# Grove_-_Air_quality_sensor_v1_3.net
KiCad netlist of a schematic drawn in EAGLE
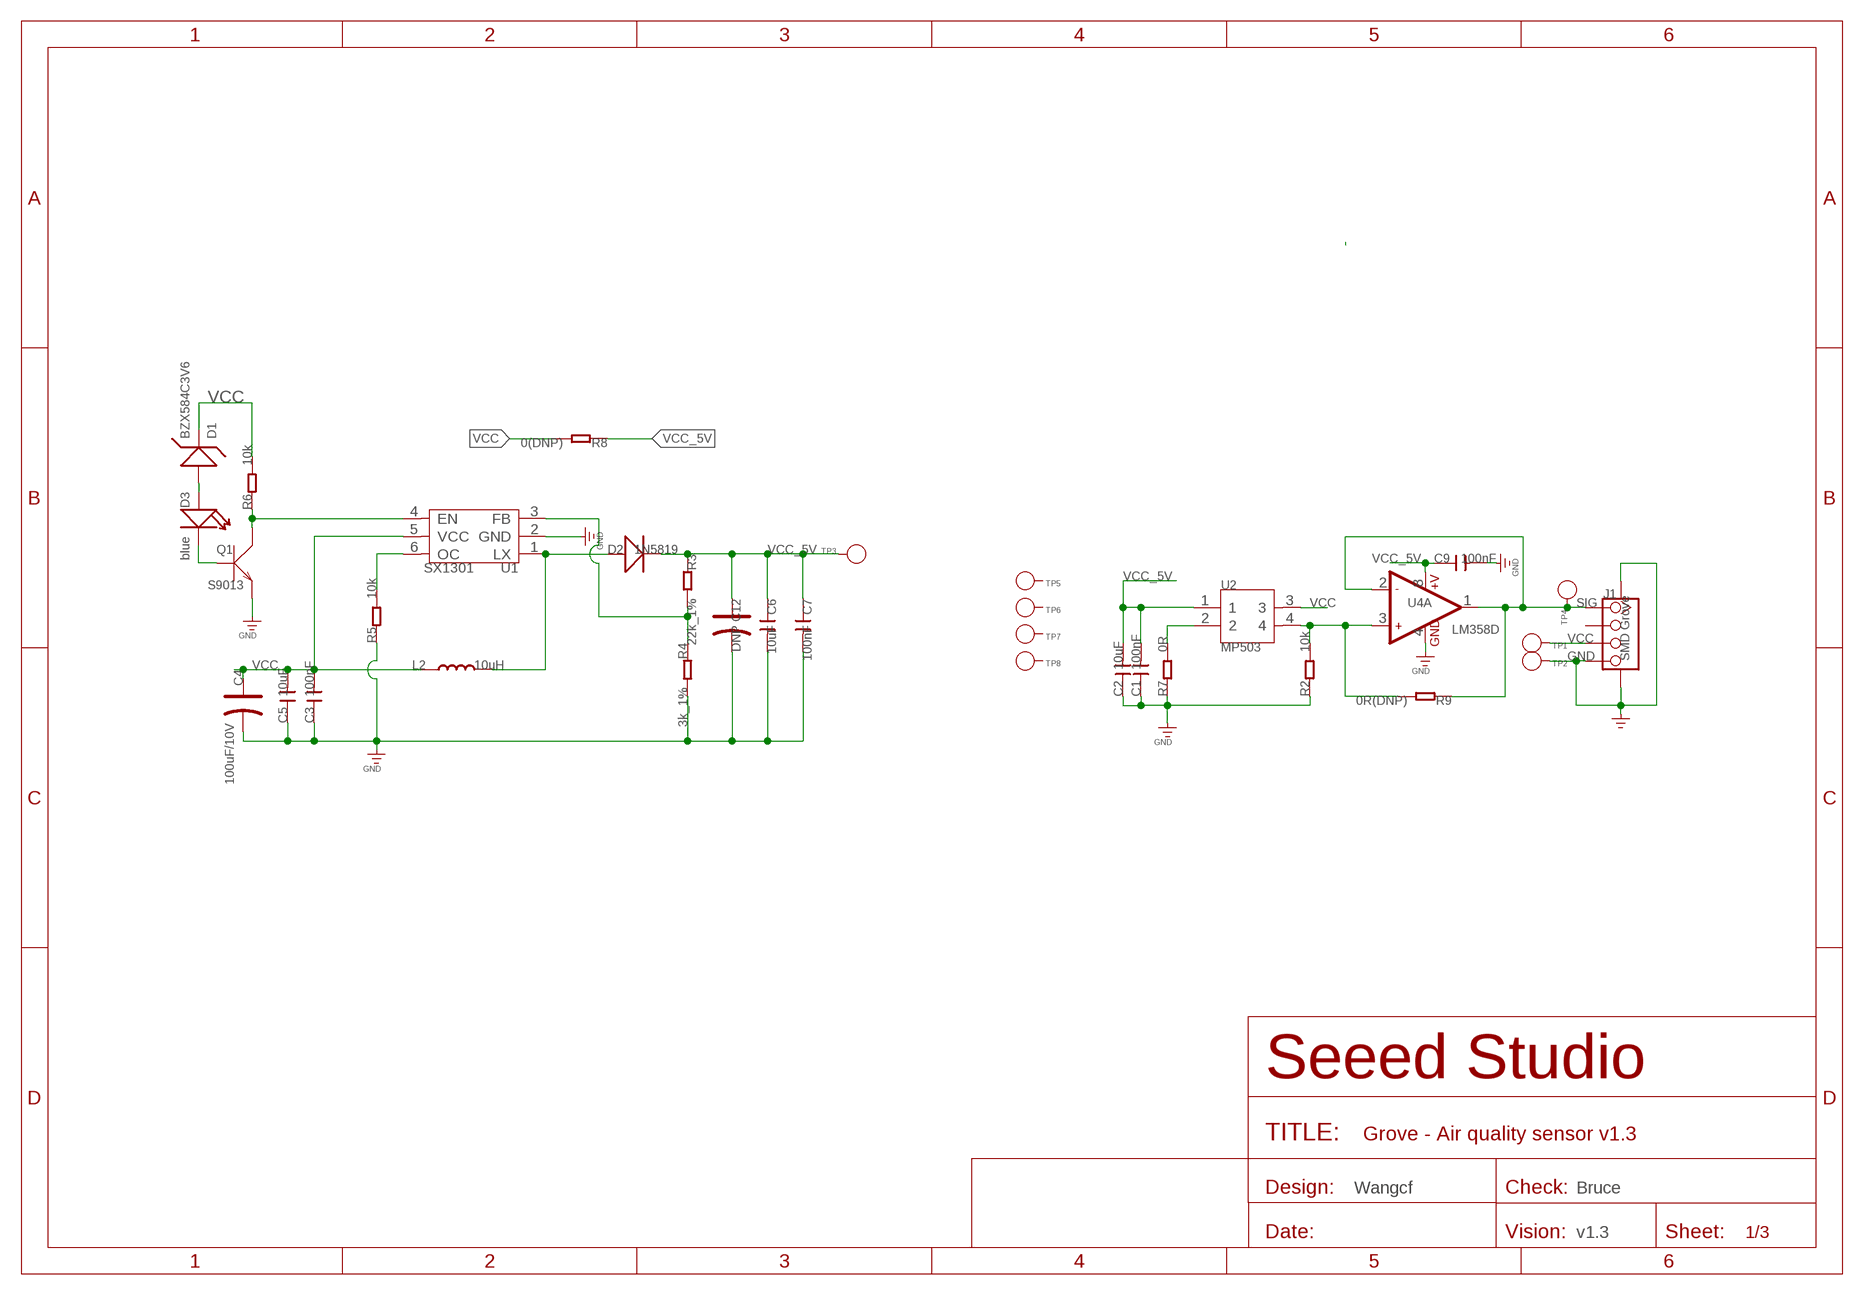
[diagram p0: schematic, sheet 1]
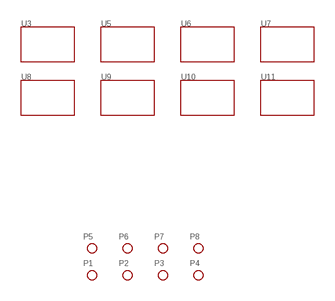
[diagram p1: schematic, sheet 3]

(export (version "E")
  (design (tool "Eeschema 10.0.6"))
  (components
    (comp (ref "P1")
      (value "PAD-MARK")
      (footprint "eagle-import:ROUND-MARK-1.0")
      (fields (field (name "PARTNO") "DNP"))
      (libsource (lib "eagle-import") (part "PAD-MARK"))
    )
    (comp (ref "P2")
      (value "PAD-MARK")
      (footprint "eagle-import:ROUND-MARK-1.0")
      (fields (field (name "PARTNO") "DNP"))
      (libsource (lib "eagle-import") (part "PAD-MARK"))
    )
    (comp (ref "P3")
      (value "PAD-MARK")
      (footprint "eagle-import:ROUND-MARK-1.0")
      (fields (field (name "PARTNO") "DNP"))
      (libsource (lib "eagle-import") (part "PAD-MARK"))
    )
    (comp (ref "P4")
      (value "PAD-MARK")
      (footprint "eagle-import:ROUND-MARK-1.0")
      (fields (field (name "PARTNO") "DNP"))
      (libsource (lib "eagle-import") (part "PAD-MARK"))
    )
    (comp (ref "P5")
      (value "PAD-MARK")
      (footprint "eagle-import:ROUND-MARK-1.0")
      (fields (field (name "PARTNO") "DNP"))
      (libsource (lib "eagle-import") (part "PAD-MARK"))
    )
    (comp (ref "P6")
      (value "PAD-MARK")
      (footprint "eagle-import:ROUND-MARK-1.0")
      (fields (field (name "PARTNO") "DNP"))
      (libsource (lib "eagle-import") (part "PAD-MARK"))
    )
    (comp (ref "P7")
      (value "PAD-MARK")
      (footprint "eagle-import:ROUND-MARK-1.0")
      (fields (field (name "PARTNO") "DNP"))
      (libsource (lib "eagle-import") (part "PAD-MARK"))
    )
    (comp (ref "P8")
      (value "PAD-MARK")
      (footprint "eagle-import:ROUND-MARK-1.0")
      (fields (field (name "PARTNO") "DNP"))
      (libsource (lib "eagle-import") (part "PAD-MARK"))
    )
    (comp (ref "U3")
      (value "TWIG'2U'")
      (footprint "eagle-import:GROVE-TEST-PLATFORM")
      (libsource (lib "eagle-import") (part "TWIG'2U'"))
    )
    (comp (ref "U5")
      (value "TWIG'2U'")
      (footprint "eagle-import:GROVE-TEST-PLATFORM")
      (libsource (lib "eagle-import") (part "TWIG'2U'"))
    )
    (comp (ref "U6")
      (value "TWIG'2U'")
      (footprint "eagle-import:GROVE-TEST-PLATFORM")
      (libsource (lib "eagle-import") (part "TWIG'2U'"))
    )
    (comp (ref "U7")
      (value "TWIG'2U'")
      (footprint "eagle-import:GROVE-TEST-PLATFORM")
      (libsource (lib "eagle-import") (part "TWIG'2U'"))
    )
    (comp (ref "U8")
      (value "TWIG'2U'")
      (footprint "eagle-import:GROVE-TEST-PLATFORM")
      (libsource (lib "eagle-import") (part "TWIG'2U'"))
    )
    (comp (ref "U9")
      (value "TWIG'2U'")
      (footprint "eagle-import:GROVE-TEST-PLATFORM")
      (libsource (lib "eagle-import") (part "TWIG'2U'"))
    )
    (comp (ref "U10")
      (value "TWIG'2U'")
      (footprint "eagle-import:GROVE-TEST-PLATFORM")
      (libsource (lib "eagle-import") (part "TWIG'2U'"))
    )
    (comp (ref "U11")
      (value "TWIG'2U'")
      (footprint "eagle-import:GROVE-TEST-PLATFORM")
      (libsource (lib "eagle-import") (part "TWIG'2U'"))
    )
    (comp (ref "C1")
      (value "100nF")
      (footprint "eagle-import:C0603")
      (libsource (lib "eagle-import") (part "C-0603"))
    )
    (comp (ref "C2")
      (value "10uF")
      (footprint "eagle-import:C0805")
      (libsource (lib "eagle-import") (part "C-0805"))
    )
    (comp (ref "C3")
      (value "100nF")
      (footprint "eagle-import:C0603")
      (libsource (lib "eagle-import") (part "C-0603"))
    )
    (comp (ref "C4")
      (value "100uF/10V")
      (footprint "eagle-import:AVX-B")
      (libsource (lib "eagle-import") (part "CAP-AVX-B"))
    )
    (comp (ref "C5")
      (value "10uF")
      (footprint "eagle-import:C0805")
      (libsource (lib "eagle-import") (part "C-0805"))
    )
    (comp (ref "C6")
      (value "10uF")
      (footprint "eagle-import:C0805")
      (libsource (lib "eagle-import") (part "C-0805"))
    )
    (comp (ref "C7")
      (value "100nF")
      (footprint "eagle-import:C0603")
      (libsource (lib "eagle-import") (part "C-0603"))
    )
    (comp (ref "C9")
      (value "100nF")
      (footprint "eagle-import:C0603")
      (libsource (lib "eagle-import") (part "C-0603"))
    )
    (comp (ref "C12")
      (value "DNP")
      (footprint "eagle-import:AVX-B")
      (libsource (lib "eagle-import") (part "CAP-AVX-B"))
    )
    (comp (ref "D1")
      (value "BZX584C3V6")
      (footprint "eagle-import:SOD-523")
      (libsource (lib "eagle-import") (part "D-ZENER-2P'BZX584CX'"))
    )
    (comp (ref "D2")
      (value "1N5819")
      (footprint "eagle-import:DO-214AC")
      (libsource (lib "eagle-import") (part "D'SMA'"))
    )
    (comp (ref "D3")
      (value "blue")
      (footprint "eagle-import:LED-0603")
      (libsource (lib "eagle-import") (part "LED'0603'"))
    )
    (comp (ref "J1")
      (value "SMD Grove")
      (footprint "eagle-import:4P-SMD-2.0")
      (libsource (lib "eagle-import") (part "TWIG-4P-2.0-SMD-FEMALE-REINFORCE'DD'"))
    )
    (comp (ref "L2")
      (value "10uH")
      (footprint "eagle-import:SD32-4R7MC")
      (libsource (lib "eagle-import") (part "CD32'4R7'"))
    )
    (comp (ref "Q1")
      (value "S9013")
      (footprint "eagle-import:SOT-23")
      (libsource (lib "eagle-import") (part "TRANSISTOR-NPN-SOT23"))
    )
    (comp (ref "R2")
      (value "10k")
      (footprint "eagle-import:R0603")
      (libsource (lib "eagle-import") (part "R-0603"))
    )
    (comp (ref "R3")
      (value "22k_1%")
      (footprint "eagle-import:R0603")
      (libsource (lib "eagle-import") (part "R-0603"))
    )
    (comp (ref "R4")
      (value "3k_1%")
      (footprint "eagle-import:R0603")
      (libsource (lib "eagle-import") (part "R-0603"))
    )
    (comp (ref "R5")
      (value "10k")
      (footprint "eagle-import:R0603")
      (libsource (lib "eagle-import") (part "R-0603"))
    )
    (comp (ref "R6")
      (value "10k")
      (footprint "eagle-import:R0603")
      (libsource (lib "eagle-import") (part "R-0603"))
    )
    (comp (ref "R7")
      (value "0R")
      (footprint "eagle-import:R0603")
      (libsource (lib "eagle-import") (part "R-0603"))
    )
    (comp (ref "R8")
      (value "0(DNP)")
      (footprint "eagle-import:R0603")
      (libsource (lib "eagle-import") (part "R-0603"))
    )
    (comp (ref "R9")
      (value "0R(DNP)")
      (footprint "eagle-import:R0603")
      (libsource (lib "eagle-import") (part "R-0603"))
    )
    (comp (ref "TP1")
      (value "PAD-TEST-POINT'4545'")
      (footprint "eagle-import:TP_4545")
      (fields (field (name "PARTNO") "DNP"))
      (libsource (lib "eagle-import") (part "PAD-TEST-POINT'4545'"))
    )
    (comp (ref "TP2")
      (value "PAD-TEST-POINT'4545'")
      (footprint "eagle-import:TP_4545")
      (fields (field (name "PARTNO") "DNP"))
      (libsource (lib "eagle-import") (part "PAD-TEST-POINT'4545'"))
    )
    (comp (ref "TP3")
      (value "PAD-TEST-POINT'4545'")
      (footprint "eagle-import:TP_4545")
      (fields (field (name "PARTNO") "DNP"))
      (libsource (lib "eagle-import") (part "PAD-TEST-POINT'4545'"))
    )
    (comp (ref "TP4")
      (value "PAD-TEST-POINT'4545'")
      (footprint "eagle-import:TP_4545")
      (fields (field (name "PARTNO") "DNP"))
      (libsource (lib "eagle-import") (part "PAD-TEST-POINT'4545'"))
    )
    (comp (ref "TP5")
      (value "PAD-TEST-POINT'4545'")
      (footprint "eagle-import:TP_4545")
      (fields (field (name "PARTNO") "DNP"))
      (libsource (lib "eagle-import") (part "PAD-TEST-POINT'4545'"))
    )
    (comp (ref "TP6")
      (value "PAD-TEST-POINT'4545'")
      (footprint "eagle-import:TP_4545")
      (fields (field (name "PARTNO") "DNP"))
      (libsource (lib "eagle-import") (part "PAD-TEST-POINT'4545'"))
    )
    (comp (ref "TP7")
      (value "PAD-TEST-POINT'4545'")
      (footprint "eagle-import:TP_4545")
      (fields (field (name "PARTNO") "DNP"))
      (libsource (lib "eagle-import") (part "PAD-TEST-POINT'4545'"))
    )
    (comp (ref "TP8")
      (value "PAD-TEST-POINT'4545'")
      (footprint "eagle-import:TP_4545")
      (fields (field (name "PARTNO") "DNP"))
      (libsource (lib "eagle-import") (part "PAD-TEST-POINT'4545'"))
    )
    (comp (ref "U1")
      (value "SX1301")
      (footprint "eagle-import:SOT23-6L")
      (libsource (lib "eagle-import") (part "SX1301"))
    )
    (comp (ref "U2")
      (value "MP503")
      (footprint "eagle-import:4P_3.1_9.4_9.4_17MM")
      (libsource (lib "eagle-import") (part "SENSOR-MP503'V1.3'"))
    )
    (comp (ref "U4")
      (value "LM358D")
      (footprint "eagle-import:SO08")
      (libsource (lib "eagle-import") (part "LMV358D"))
    )
  )
  (nets
    (net (code "1") (name "GND") (class "Default")
      (node (ref "C1") (pin "1") (pinfunction "1_1") (pintype "passive"))
      (node (ref "C12") (pin "-") (pinfunction "-_-") (pintype "passive"))
      (node (ref "C2") (pin "1") (pinfunction "1_1") (pintype "passive"))
      (node (ref "C3") (pin "1") (pinfunction "1_1") (pintype "passive"))
      (node (ref "C4") (pin "-") (pinfunction "-_-") (pintype "passive"))
      (node (ref "C5") (pin "1") (pinfunction "1_1") (pintype "passive"))
      (node (ref "C6") (pin "2") (pinfunction "2_2") (pintype "passive"))
      (node (ref "C7") (pin "2") (pinfunction "2_2") (pintype "passive"))
      (node (ref "C9") (pin "2") (pinfunction "2_2") (pintype "passive"))
      (node (ref "J1") (pin "4") (pinfunction "4_4") (pintype "bidirectional"))
      (node (ref "J1") (pin "SS1") (pinfunction "SS1_SS1") (pintype "bidirectional"))
      (node (ref "J1") (pin "SS2") (pinfunction "SS2_SS2") (pintype "bidirectional"))
      (node (ref "Q1") (pin "2") (pinfunction "E_2") (pintype "passive"))
      (node (ref "R2") (pin "1") (pinfunction "1_1") (pintype "passive"))
      (node (ref "R4") (pin "2") (pinfunction "2_2") (pintype "passive"))
      (node (ref "R5") (pin "1") (pinfunction "1_1") (pintype "passive"))
      (node (ref "R7") (pin "1") (pinfunction "1_1") (pintype "passive"))
      (node (ref "TP2") (pin "T") (pinfunction "T_T") (pintype "bidirectional"))
      (node (ref "U1") (pin "2") (pinfunction "GND_2") (pintype "bidirectional"))
      (node (ref "U4") (pin "4") (pinfunction "GND_4") (pintype "power_in"))
    )
    (net (code "2") (name "Net-(D1-Pad+)") (class "Default")
      (node (ref "D1") (pin "+") (pinfunction "+_+") (pintype "bidirectional"))
      (node (ref "D3") (pin "+") (pinfunction "+_+") (pintype "passive"))
    )
    (net (code "3") (name "Net-(D2-+)") (class "Default")
      (node (ref "D2") (pin "1") (pinfunction "+_1") (pintype "passive"))
      (node (ref "L2") (pin "2") (pinfunction "2_2") (pintype "passive"))
      (node (ref "U1") (pin "1") (pinfunction "LX_1") (pintype "bidirectional"))
    )
    (net (code "4") (name "Net-(Q1-B)") (class "Default")
      (node (ref "D3") (pin "-") (pinfunction "-_-") (pintype "passive"))
      (node (ref "Q1") (pin "1") (pinfunction "B_1") (pintype "passive"))
    )
    (net (code "5") (name "Net-(Q1-C)") (class "Default")
      (node (ref "Q1") (pin "3") (pinfunction "C_3") (pintype "passive"))
      (node (ref "R6") (pin "1") (pinfunction "1_1") (pintype "passive"))
      (node (ref "U1") (pin "4") (pinfunction "EN_4") (pintype "bidirectional"))
    )
    (net (code "6") (name "Net-(R7-Pad2)") (class "Default")
      (node (ref "R7") (pin "2") (pinfunction "2_2") (pintype "passive"))
      (node (ref "U2") (pin "2") (pinfunction "2_2") (pintype "bidirectional"))
    )
    (net (code "7") (name "Net-(U1-FB)") (class "Default")
      (node (ref "R3") (pin "2") (pinfunction "2_2") (pintype "passive"))
      (node (ref "R4") (pin "1") (pinfunction "1_1") (pintype "passive"))
      (node (ref "U1") (pin "3") (pinfunction "FB_3") (pintype "bidirectional"))
    )
    (net (code "8") (name "Net-(U1-OC)") (class "Default")
      (node (ref "R5") (pin "2") (pinfunction "2_2") (pintype "passive"))
      (node (ref "U1") (pin "6") (pinfunction "OC_6") (pintype "bidirectional"))
    )
    (net (code "9") (name "Net-(U4A-+IN1)") (class "Default")
      (node (ref "R2") (pin "2") (pinfunction "2_2") (pintype "passive"))
      (node (ref "R9") (pin "2") (pinfunction "2_2") (pintype "passive"))
      (node (ref "U2") (pin "4") (pinfunction "4_4") (pintype "bidirectional"))
      (node (ref "U4") (pin "3") (pinfunction "+IN1_3") (pintype "input"))
    )
    (net (code "10") (name "SIG") (class "Default")
      (node (ref "J1") (pin "1") (pinfunction "1_1") (pintype "bidirectional"))
      (node (ref "R9") (pin "1") (pinfunction "1_1") (pintype "passive"))
      (node (ref "TP4") (pin "T") (pinfunction "T_T") (pintype "bidirectional"))
      (node (ref "U4") (pin "1") (pinfunction "OUT1_1") (pintype "output"))
      (node (ref "U4") (pin "2") (pinfunction "-IN1_2") (pintype "input"))
    )
    (net (code "11") (name "VCC") (class "Default")
      (node (ref "C3") (pin "2") (pinfunction "2_2") (pintype "passive"))
      (node (ref "C4") (pin "+") (pinfunction "+_+") (pintype "passive"))
      (node (ref "C5") (pin "2") (pinfunction "2_2") (pintype "passive"))
      (node (ref "D1") (pin "-") (pinfunction "-_-") (pintype "bidirectional"))
      (node (ref "J1") (pin "3") (pinfunction "3_3") (pintype "bidirectional"))
      (node (ref "L2") (pin "1") (pinfunction "1_1") (pintype "passive"))
      (node (ref "R6") (pin "2") (pinfunction "2_2") (pintype "passive"))
      (node (ref "R8") (pin "2") (pinfunction "2_2") (pintype "passive"))
      (node (ref "TP1") (pin "T") (pinfunction "T_T") (pintype "bidirectional"))
      (node (ref "U1") (pin "5") (pinfunction "VCC_5") (pintype "bidirectional"))
      (node (ref "U2") (pin "3") (pinfunction "3_3") (pintype "bidirectional"))
    )
    (net (code "12") (name "VCC_5V") (class "Default")
      (node (ref "C1") (pin "2") (pinfunction "2_2") (pintype "passive"))
      (node (ref "C12") (pin "+") (pinfunction "+_+") (pintype "passive"))
      (node (ref "C2") (pin "2") (pinfunction "2_2") (pintype "passive"))
      (node (ref "C6") (pin "1") (pinfunction "1_1") (pintype "passive"))
      (node (ref "C7") (pin "1") (pinfunction "1_1") (pintype "passive"))
      (node (ref "C9") (pin "1") (pinfunction "1_1") (pintype "passive"))
      (node (ref "D2") (pin "2") (pinfunction "-_2") (pintype "passive"))
      (node (ref "R3") (pin "1") (pinfunction "1_1") (pintype "passive"))
      (node (ref "R8") (pin "1") (pinfunction "1_1") (pintype "passive"))
      (node (ref "TP3") (pin "T") (pinfunction "T_T") (pintype "bidirectional"))
      (node (ref "U2") (pin "1") (pinfunction "1_1") (pintype "bidirectional"))
      (node (ref "U4") (pin "8") (pinfunction "+V_8") (pintype "power_in"))
    )
    (net (code "13") (name "unconnected-(J1-Pad2)") (class "Default")
      (node (ref "J1") (pin "2") (pinfunction "2_2") (pintype "bidirectional"))
    )
    (net (code "14") (name "unconnected-(TP5-PadT)") (class "Default")
      (node (ref "TP5") (pin "T") (pinfunction "T_T") (pintype "bidirectional"))
    )
    (net (code "15") (name "unconnected-(TP6-PadT)") (class "Default")
      (node (ref "TP6") (pin "T") (pinfunction "T_T") (pintype "bidirectional"))
    )
    (net (code "16") (name "unconnected-(TP7-PadT)") (class "Default")
      (node (ref "TP7") (pin "T") (pinfunction "T_T") (pintype "bidirectional"))
    )
    (net (code "17") (name "unconnected-(TP8-PadT)") (class "Default")
      (node (ref "TP8") (pin "T") (pinfunction "T_T") (pintype "bidirectional"))
    )
  )
)
